# EPS_MPPT_X_OR_Solar.net
KiCad netlist of a schematic drawn in Altium Designer
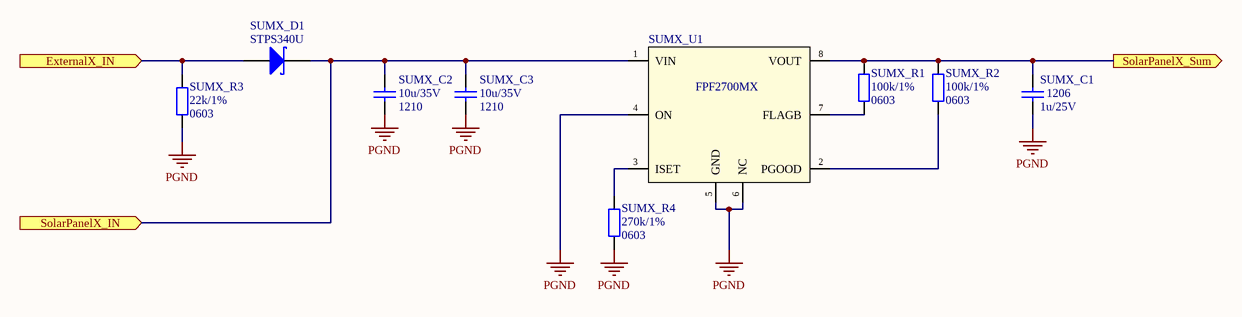
[diagram p0: EPS_MPPT_X_OR_Solar.SchDoc]

(export (version "E")
  (design (tool "Eeschema 10.0.6"))
  (components
    (comp (ref "SUMX_C1")
      (value "1u/25V")
      (footprint "SMD_Capacitor_1206")
      (description "Ceramic Cap Kemet COTS 1u/25V X7R 1206")
      (fields
        (field (name "MANUFACTURERPARTNUMBER") "C1206T105K3RALTU")
        (field (name "MANUFACTURER") "Kemet")
        (field (name "PACKAGE") "1206")
      )
      (libsource (lib "capacitors") (part "Cer_C1206T105K3RALTU"))
    )
    (comp (ref "SUMX_C2")
      (value "10u/35V")
      (footprint "SMD_Capacitor_1210")
      (description "Ceramic Cap Murata Automotive 10u/35V X7S 1210")
      (fields
        (field (name "MANUFACTURER") "Murata")
        (field (name "MANUFACTURERPARTNUMBER") "GCM32EC7YA106KA03K")
        (field (name "PACKAGE") "1210")
      )
      (libsource (lib "capacitors") (part "Cer_GCM32EC7YA106KA03K"))
    )
    (comp (ref "SUMX_C3")
      (value "10u/35V")
      (footprint "SMD_Capacitor_1210")
      (description "Ceramic Cap Murata Automotive 10u/35V X7S 1210")
      (fields
        (field (name "MANUFACTURER") "Murata")
        (field (name "MANUFACTURERPARTNUMBER") "GCM32EC7YA106KA03K")
        (field (name "PACKAGE") "1210")
      )
      (libsource (lib "capacitors") (part "Cer_GCM32EC7YA106KA03K"))
    )
    (comp (ref "SUMX_D1")
      (value "STPS340U")
      (footprint "DO-214AA")
      (description "3A/40V Power Schottky Rectifier.")
      (fields (field (name "MANUFACTURER") "STMicroelectronics"))
      (libsource (lib "diodes") (part "STPS340x"))
    )
    (comp (ref "SUMX_R1")
      (value "100k/1%")
      (footprint "SMD_Resistor_0603")
      (fields (field (name "PACKAGE") "0603"))
      (libsource (lib "resistors") (part "Res"))
    )
    (comp (ref "SUMX_R2")
      (value "100k/1%")
      (footprint "SMD_Resistor_0603")
      (fields (field (name "PACKAGE") "0603"))
      (libsource (lib "resistors") (part "Res"))
    )
    (comp (ref "SUMX_R3")
      (value "22k/1%")
      (footprint "SMD_Resistor_0603")
      (fields (field (name "PACKAGE") "0603"))
      (libsource (lib "resistors") (part "Res"))
    )
    (comp (ref "SUMX_R4")
      (value "270k/1%")
      (footprint "SMD_Resistor_0603")
      (fields (field (name "PACKAGE") "0603"))
      (libsource (lib "resistors") (part "Res"))
    )
    (comp (ref "SUMX_U1")
      (value "FPF2700MX")
      (footprint "SOIC-8-N")
      (description "Adj over-current protection 0.4-2A, Load Switch")
      (fields (field (name "MANUFACTURER") "Fairchild Semiconductor"))
      (libsource (lib "microcircuits") (part "FPF2700MX"))
    )
  )
  (nets
    (net (code "1") (name "/ExternalX_IN") (class "Default")
      (node (ref "SUMX_D1") (pin "A") (pinfunction "A_A") (pintype "passive"))
      (node (ref "SUMX_R3") (pin "1") (pinfunction "1_1") (pintype "passive"))
    )
    (net (code "2") (name "/SolarPanelX_IN") (class "Default")
      (node (ref "SUMX_C2") (pin "1") (pinfunction "1_1") (pintype "passive"))
      (node (ref "SUMX_C3") (pin "1") (pinfunction "1_1") (pintype "passive"))
      (node (ref "SUMX_D1") (pin "K") (pinfunction "K_K") (pintype "passive"))
      (node (ref "SUMX_U1") (pin "1") (pinfunction "VIN_1") (pintype "passive"))
    )
    (net (code "3") (name "/SolarPanelX_Sum") (class "Default")
      (node (ref "SUMX_C1") (pin "1") (pinfunction "1_1") (pintype "passive"))
      (node (ref "SUMX_R1") (pin "1") (pinfunction "1_1") (pintype "passive"))
      (node (ref "SUMX_R2") (pin "1") (pinfunction "1_1") (pintype "passive"))
      (node (ref "SUMX_U1") (pin "8") (pinfunction "VOUT_8") (pintype "passive"))
    )
    (net (code "4") (name "Net-(SUMX_U1-FLAGB)") (class "Default")
      (node (ref "SUMX_R1") (pin "2") (pinfunction "2_2") (pintype "passive"))
      (node (ref "SUMX_U1") (pin "7") (pinfunction "FLAGB_7") (pintype "passive"))
    )
    (net (code "5") (name "Net-(SUMX_U1-ISET)") (class "Default")
      (node (ref "SUMX_R4") (pin "1") (pinfunction "1_1") (pintype "passive"))
      (node (ref "SUMX_U1") (pin "3") (pinfunction "ISET_3") (pintype "passive"))
    )
    (net (code "6") (name "Net-(SUMX_U1-PGOOD)") (class "Default")
      (node (ref "SUMX_R2") (pin "2") (pinfunction "2_2") (pintype "passive"))
      (node (ref "SUMX_U1") (pin "2") (pinfunction "PGOOD_2") (pintype "passive"))
    )
    (net (code "7") (name "PGND") (class "Default")
      (node (ref "SUMX_C1") (pin "2") (pinfunction "2_2") (pintype "passive"))
      (node (ref "SUMX_C2") (pin "2") (pinfunction "2_2") (pintype "passive"))
      (node (ref "SUMX_C3") (pin "2") (pinfunction "2_2") (pintype "passive"))
      (node (ref "SUMX_R3") (pin "2") (pinfunction "2_2") (pintype "passive"))
      (node (ref "SUMX_R4") (pin "2") (pinfunction "2_2") (pintype "passive"))
      (node (ref "SUMX_U1") (pin "4") (pinfunction "ON_4") (pintype "passive"))
      (node (ref "SUMX_U1") (pin "5") (pinfunction "GND_5") (pintype "passive"))
      (node (ref "SUMX_U1") (pin "6") (pinfunction "NC_6") (pintype "passive"))
    )
  )
)
